# Conn6_5.net
KiCad netlist of a schematic drawn in Altium Designer
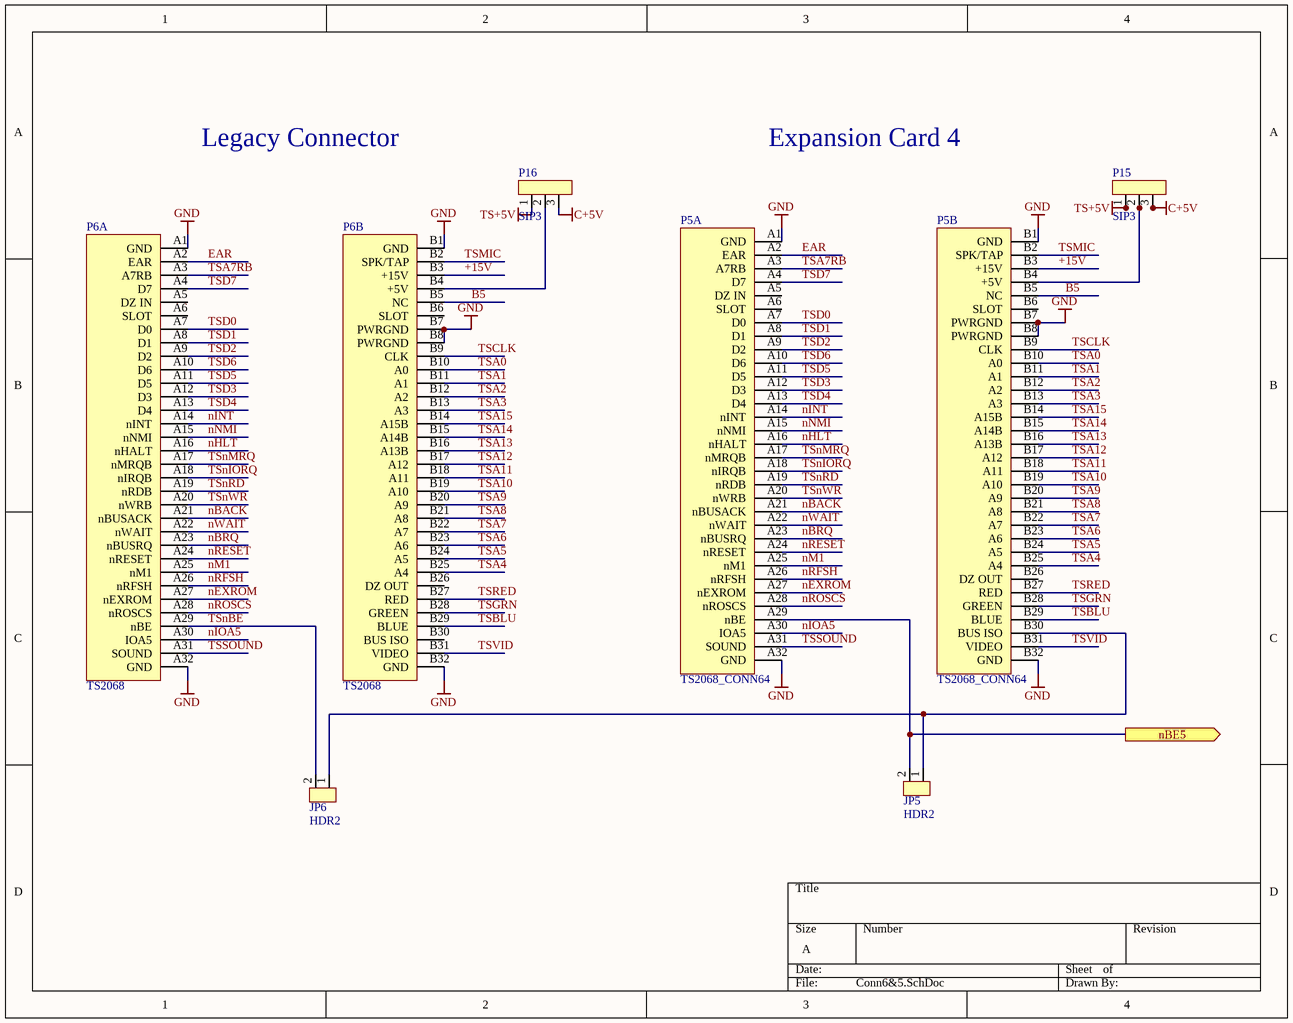
[diagram p0: Conn6&5.SchDoc]

(export (version "E")
  (design (tool "Eeschema 10.0.6"))
  (components
    (comp (ref "JP5") (value "HDR2") (footprint "HDR2") (libsource (lib "Connectors") (part "HDR2")))
    (comp (ref "JP6") (value "HDR2") (footprint "HDR2") (libsource (lib "Connectors") (part "HDR2")))
    (comp (ref "P5")
      (value "TS2068_CONN64")
      (footprint "64CARDEDGE")
      (description "64 Position Female Connector Non Specified - Dual Edge Gold 0.100\" (2.54mm) Black")
      (fields (field (name "MFG") "TD"))
      (libsource (lib "Connectors") (part "TS2068_CONN64"))
    )
    (comp (ref "P6") (value "TS2068") (footprint "TS2068") (libsource (lib "Modules") (part "TS2068")))
    (comp (ref "P15") (value "SIP3") (footprint "SIP3") (libsource (lib "Connectors") (part "SIP3")))
    (comp (ref "P16") (value "SIP3") (footprint "SIP3") (libsource (lib "Connectors") (part "SIP3")))
  )
  (nets
    (net (code "1") (name "/+15V") (class "Default")
      (node (ref "P5") (pin "B3") (pinfunction "+15V_B3") (pintype "passive"))
      (node (ref "P6") (pin "B3") (pinfunction "+15V_B3") (pintype "passive"))
    )
    (net (code "2") (name "/B5") (class "Default")
      (node (ref "P5") (pin "B5") (pinfunction "NC_B5") (pintype "passive"))
      (node (ref "P6") (pin "B5") (pinfunction "NC_B5") (pintype "passive"))
    )
    (net (code "3") (name "/EAR") (class "Default")
      (node (ref "P5") (pin "A2") (pinfunction "EAR_A2") (pintype "passive"))
      (node (ref "P6") (pin "A2") (pinfunction "EAR_A2") (pintype "passive"))
    )
    (net (code "4") (name "/TSA0") (class "Default")
      (node (ref "P5") (pin "B10") (pinfunction "A0_B10") (pintype "passive"))
      (node (ref "P6") (pin "B10") (pinfunction "A0_B10") (pintype "passive"))
    )
    (net (code "5") (name "/TSA1") (class "Default")
      (node (ref "P5") (pin "B11") (pinfunction "A1_B11") (pintype "passive"))
      (node (ref "P6") (pin "B11") (pinfunction "A1_B11") (pintype "passive"))
    )
    (net (code "6") (name "/TSA2") (class "Default")
      (node (ref "P5") (pin "B12") (pinfunction "A2_B12") (pintype "passive"))
      (node (ref "P6") (pin "B12") (pinfunction "A2_B12") (pintype "passive"))
    )
    (net (code "7") (name "/TSA3") (class "Default")
      (node (ref "P5") (pin "B13") (pinfunction "A3_B13") (pintype "passive"))
      (node (ref "P6") (pin "B13") (pinfunction "A3_B13") (pintype "passive"))
    )
    (net (code "8") (name "/TSA4") (class "Default")
      (node (ref "P5") (pin "B25") (pinfunction "A4_B25") (pintype "passive"))
      (node (ref "P6") (pin "B25") (pinfunction "A4_B25") (pintype "passive"))
    )
    (net (code "9") (name "/TSA5") (class "Default")
      (node (ref "P5") (pin "B24") (pinfunction "A5_B24") (pintype "passive"))
      (node (ref "P6") (pin "B24") (pinfunction "A5_B24") (pintype "passive"))
    )
    (net (code "10") (name "/TSA6") (class "Default")
      (node (ref "P5") (pin "B23") (pinfunction "A6_B23") (pintype "passive"))
      (node (ref "P6") (pin "B23") (pinfunction "A6_B23") (pintype "passive"))
    )
    (net (code "11") (name "/TSA7") (class "Default")
      (node (ref "P5") (pin "B22") (pinfunction "A7_B22") (pintype "passive"))
      (node (ref "P6") (pin "B22") (pinfunction "A7_B22") (pintype "passive"))
    )
    (net (code "12") (name "/TSA7RB") (class "Default")
      (node (ref "P5") (pin "A3") (pinfunction "A7RB_A3") (pintype "passive"))
      (node (ref "P6") (pin "A3") (pinfunction "A7RB_A3") (pintype "passive"))
    )
    (net (code "13") (name "/TSA8") (class "Default")
      (node (ref "P5") (pin "B21") (pinfunction "A8_B21") (pintype "passive"))
      (node (ref "P6") (pin "B21") (pinfunction "A8_B21") (pintype "passive"))
    )
    (net (code "14") (name "/TSA9") (class "Default")
      (node (ref "P5") (pin "B20") (pinfunction "A9_B20") (pintype "passive"))
      (node (ref "P6") (pin "B20") (pinfunction "A9_B20") (pintype "passive"))
    )
    (net (code "15") (name "/TSA10") (class "Default")
      (node (ref "P5") (pin "B19") (pinfunction "A10_B19") (pintype "passive"))
      (node (ref "P6") (pin "B19") (pinfunction "A10_B19") (pintype "passive"))
    )
    (net (code "16") (name "/TSA11") (class "Default")
      (node (ref "P5") (pin "B18") (pinfunction "A11_B18") (pintype "passive"))
      (node (ref "P6") (pin "B18") (pinfunction "A11_B18") (pintype "passive"))
    )
    (net (code "17") (name "/TSA12") (class "Default")
      (node (ref "P5") (pin "B17") (pinfunction "A12_B17") (pintype "passive"))
      (node (ref "P6") (pin "B17") (pinfunction "A12_B17") (pintype "passive"))
    )
    (net (code "18") (name "/TSA13") (class "Default")
      (node (ref "P5") (pin "B16") (pinfunction "A13B_B16") (pintype "passive"))
      (node (ref "P6") (pin "B16") (pinfunction "A13B_B16") (pintype "passive"))
    )
    (net (code "19") (name "/TSA14") (class "Default")
      (node (ref "P5") (pin "B15") (pinfunction "A14B_B15") (pintype "passive"))
      (node (ref "P6") (pin "B15") (pinfunction "A14B_B15") (pintype "passive"))
    )
    (net (code "20") (name "/TSA15") (class "Default")
      (node (ref "P5") (pin "B14") (pinfunction "A15B_B14") (pintype "passive"))
      (node (ref "P6") (pin "B14") (pinfunction "A15B_B14") (pintype "passive"))
    )
    (net (code "21") (name "/TSBLU") (class "Default")
      (node (ref "P5") (pin "B29") (pinfunction "BLUE_B29") (pintype "passive"))
      (node (ref "P6") (pin "B29") (pinfunction "BLUE_B29") (pintype "passive"))
    )
    (net (code "22") (name "/TSCLK") (class "Default")
      (node (ref "P5") (pin "B9") (pinfunction "CLK_B9") (pintype "passive"))
      (node (ref "P6") (pin "B9") (pinfunction "CLK_B9") (pintype "passive"))
    )
    (net (code "23") (name "/TSD0") (class "Default")
      (node (ref "P5") (pin "A7") (pinfunction "D0_A7") (pintype "passive"))
      (node (ref "P6") (pin "A7") (pinfunction "D0_A7") (pintype "passive"))
    )
    (net (code "24") (name "/TSD1") (class "Default")
      (node (ref "P5") (pin "A8") (pinfunction "D1_A8") (pintype "passive"))
      (node (ref "P6") (pin "A8") (pinfunction "D1_A8") (pintype "passive"))
    )
    (net (code "25") (name "/TSD2") (class "Default")
      (node (ref "P5") (pin "A9") (pinfunction "D2_A9") (pintype "passive"))
      (node (ref "P6") (pin "A9") (pinfunction "D2_A9") (pintype "passive"))
    )
    (net (code "26") (name "/TSD3") (class "Default")
      (node (ref "P5") (pin "A12") (pinfunction "D3_A12") (pintype "passive"))
      (node (ref "P6") (pin "A12") (pinfunction "D3_A12") (pintype "passive"))
    )
    (net (code "27") (name "/TSD4") (class "Default")
      (node (ref "P5") (pin "A13") (pinfunction "D4_A13") (pintype "passive"))
      (node (ref "P6") (pin "A13") (pinfunction "D4_A13") (pintype "passive"))
    )
    (net (code "28") (name "/TSD5") (class "Default")
      (node (ref "P5") (pin "A11") (pinfunction "D5_A11") (pintype "passive"))
      (node (ref "P6") (pin "A11") (pinfunction "D5_A11") (pintype "passive"))
    )
    (net (code "29") (name "/TSD6") (class "Default")
      (node (ref "P5") (pin "A10") (pinfunction "D6_A10") (pintype "passive"))
      (node (ref "P6") (pin "A10") (pinfunction "D6_A10") (pintype "passive"))
    )
    (net (code "30") (name "/TSD7") (class "Default")
      (node (ref "P5") (pin "A4") (pinfunction "D7_A4") (pintype "passive"))
      (node (ref "P6") (pin "A4") (pinfunction "D7_A4") (pintype "passive"))
    )
    (net (code "31") (name "/TSGRN") (class "Default")
      (node (ref "P5") (pin "B28") (pinfunction "GREEN_B28") (pintype "passive"))
      (node (ref "P6") (pin "B28") (pinfunction "GREEN_B28") (pintype "passive"))
    )
    (net (code "32") (name "/TSMIC") (class "Default")
      (node (ref "P5") (pin "B2") (pinfunction "SPK/TAP_B2") (pintype "passive"))
      (node (ref "P6") (pin "B2") (pinfunction "SPK/TAP_B2") (pintype "passive"))
    )
    (net (code "33") (name "/TSRED") (class "Default")
      (node (ref "P5") (pin "B27") (pinfunction "RED_B27") (pintype "passive"))
      (node (ref "P6") (pin "B27") (pinfunction "RED_B27") (pintype "passive"))
    )
    (net (code "34") (name "/TSSOUND") (class "Default")
      (node (ref "P5") (pin "A31") (pinfunction "SOUND_A31") (pintype "passive"))
      (node (ref "P6") (pin "A31") (pinfunction "SOUND_A31") (pintype "passive"))
    )
    (net (code "35") (name "/TSVID") (class "Default")
      (node (ref "P5") (pin "B31") (pinfunction "VIDEO_B31") (pintype "passive"))
      (node (ref "P6") (pin "B31") (pinfunction "VIDEO_B31") (pintype "passive"))
    )
    (net (code "36") (name "/TSnBE") (class "Default")
      (node (ref "JP6") (pin "2") (pintype "passive"))
      (node (ref "P6") (pin "A29") (pinfunction "nBE_A29") (pintype "passive"))
    )
    (net (code "37") (name "/TSnIORQ") (class "Default")
      (node (ref "P5") (pin "A18") (pinfunction "nIRQB_A18") (pintype "passive"))
      (node (ref "P6") (pin "A18") (pinfunction "nIRQB_A18") (pintype "passive"))
    )
    (net (code "38") (name "/TSnMRQ") (class "Default")
      (node (ref "P5") (pin "A17") (pinfunction "nMRQB_A17") (pintype "passive"))
      (node (ref "P6") (pin "A17") (pinfunction "nMRQB_A17") (pintype "passive"))
    )
    (net (code "39") (name "/TSnRD") (class "Default")
      (node (ref "P5") (pin "A19") (pinfunction "nRDB_A19") (pintype "passive"))
      (node (ref "P6") (pin "A19") (pinfunction "nRDB_A19") (pintype "passive"))
    )
    (net (code "40") (name "/TSnWR") (class "Default")
      (node (ref "P5") (pin "A20") (pinfunction "nWRB_A20") (pintype "passive"))
      (node (ref "P6") (pin "A20") (pinfunction "nWRB_A20") (pintype "passive"))
    )
    (net (code "41") (name "/nBACK") (class "Default")
      (node (ref "P5") (pin "A21") (pinfunction "nBUSACK_A21") (pintype "passive"))
      (node (ref "P6") (pin "A21") (pinfunction "nBUSACK_A21") (pintype "passive"))
    )
    (net (code "42") (name "/nBE5") (class "Default")
      (node (ref "JP5") (pin "2") (pintype "passive"))
      (node (ref "P5") (pin "A29") (pinfunction "nBE_A29") (pintype "passive"))
    )
    (net (code "43") (name "/nBRQ") (class "Default")
      (node (ref "P5") (pin "A23") (pinfunction "nBUSRQ_A23") (pintype "passive"))
      (node (ref "P6") (pin "A23") (pinfunction "nBUSRQ_A23") (pintype "passive"))
    )
    (net (code "44") (name "/nEXROM") (class "Default")
      (node (ref "P5") (pin "A27") (pinfunction "nEXROM_A27") (pintype "passive"))
      (node (ref "P6") (pin "A27") (pinfunction "nEXROM_A27") (pintype "passive"))
    )
    (net (code "45") (name "/nHLT") (class "Default")
      (node (ref "P5") (pin "A16") (pinfunction "nHALT_A16") (pintype "passive"))
      (node (ref "P6") (pin "A16") (pinfunction "nHALT_A16") (pintype "passive"))
    )
    (net (code "46") (name "/nINT") (class "Default")
      (node (ref "P5") (pin "A14") (pinfunction "nINT_A14") (pintype "passive"))
      (node (ref "P6") (pin "A14") (pinfunction "nINT_A14") (pintype "passive"))
    )
    (net (code "47") (name "/nIOA5") (class "Default")
      (node (ref "P5") (pin "A30") (pinfunction "IOA5_A30") (pintype "passive"))
      (node (ref "P6") (pin "A30") (pinfunction "IOA5_A30") (pintype "passive"))
    )
    (net (code "48") (name "/nM1") (class "Default")
      (node (ref "P5") (pin "A25") (pinfunction "nM1_A25") (pintype "passive"))
      (node (ref "P6") (pin "A25") (pinfunction "nM1_A25") (pintype "passive"))
    )
    (net (code "49") (name "/nNMI") (class "Default")
      (node (ref "P5") (pin "A15") (pinfunction "nNMI_A15") (pintype "passive"))
      (node (ref "P6") (pin "A15") (pinfunction "nNMI_A15") (pintype "passive"))
    )
    (net (code "50") (name "/nRESET") (class "Default")
      (node (ref "P5") (pin "A24") (pinfunction "nRESET_A24") (pintype "passive"))
      (node (ref "P6") (pin "A24") (pinfunction "nRESET_A24") (pintype "passive"))
    )
    (net (code "51") (name "/nRFSH") (class "Default")
      (node (ref "P5") (pin "A26") (pinfunction "nRFSH_A26") (pintype "passive"))
      (node (ref "P6") (pin "A26") (pinfunction "nRFSH_A26") (pintype "passive"))
    )
    (net (code "52") (name "/nROSCS") (class "Default")
      (node (ref "P5") (pin "A28") (pinfunction "nROSCS_A28") (pintype "passive"))
      (node (ref "P6") (pin "A28") (pinfunction "nROSCS_A28") (pintype "passive"))
    )
    (net (code "53") (name "/nWAIT") (class "Default")
      (node (ref "P5") (pin "A22") (pinfunction "nWAIT_A22") (pintype "passive"))
      (node (ref "P6") (pin "A22") (pinfunction "nWAIT_A22") (pintype "passive"))
    )
    (net (code "54") (name "C+5V") (class "Default")
      (node (ref "P15") (pin "3") (pintype "passive"))
      (node (ref "P16") (pin "3") (pintype "passive"))
    )
    (net (code "55") (name "GND") (class "Default")
      (node (ref "P5") (pin "A1") (pinfunction "GND_A1") (pintype "passive"))
      (node (ref "P5") (pin "A32") (pinfunction "GND_A32") (pintype "passive"))
      (node (ref "P5") (pin "B1") (pinfunction "GND_B1") (pintype "passive"))
      (node (ref "P5") (pin "B32") (pinfunction "GND_B32") (pintype "passive"))
      (node (ref "P5") (pin "B7") (pinfunction "PWRGND_B7") (pintype "passive"))
      (node (ref "P5") (pin "B8") (pinfunction "PWRGND_B8") (pintype "passive"))
      (node (ref "P6") (pin "A1") (pinfunction "GND_A1") (pintype "passive"))
      (node (ref "P6") (pin "A32") (pinfunction "GND_A32") (pintype "passive"))
      (node (ref "P6") (pin "B1") (pinfunction "GND_B1") (pintype "passive"))
      (node (ref "P6") (pin "B32") (pinfunction "GND_B32") (pintype "passive"))
      (node (ref "P6") (pin "B7") (pinfunction "PWRGND_B7") (pintype "passive"))
      (node (ref "P6") (pin "B8") (pinfunction "PWRGND_B8") (pintype "passive"))
    )
    (net (code "56") (name "Net-(P5B-+5V)") (class "Default")
      (node (ref "P15") (pin "2") (pintype "passive"))
      (node (ref "P5") (pin "B4") (pinfunction "+5V_B4") (pintype "passive"))
    )
    (net (code "57") (name "Net-(P5B-BUS_ISO)") (class "Default")
      (node (ref "JP5") (pin "1") (pintype "passive"))
      (node (ref "JP6") (pin "1") (pintype "passive"))
      (node (ref "P5") (pin "B30") (pinfunction "BUS_ISO_B30") (pintype "passive"))
    )
    (net (code "58") (name "Net-(P6B-+5V)") (class "Default")
      (node (ref "P16") (pin "2") (pintype "passive"))
      (node (ref "P6") (pin "B4") (pinfunction "+5V_B4") (pintype "passive"))
    )
    (net (code "59") (name "TS+5V") (class "Default")
      (node (ref "P15") (pin "1") (pintype "passive"))
      (node (ref "P16") (pin "1") (pintype "passive"))
    )
    (net (code "60") (name "unconnected-(P5A-DZ_IN-PadA5)") (class "Default")
      (node (ref "P5") (pin "A5") (pinfunction "DZ_IN_A5") (pintype "passive"))
    )
    (net (code "61") (name "unconnected-(P5A-SLOT-PadA6)") (class "Default")
      (node (ref "P5") (pin "A6") (pinfunction "SLOT_A6") (pintype "passive"))
    )
    (net (code "62") (name "unconnected-(P5B-DZ_OUT-PadB26)") (class "Default")
      (node (ref "P5") (pin "B26") (pinfunction "DZ_OUT_B26") (pintype "passive"))
    )
    (net (code "63") (name "unconnected-(P5B-SLOT-PadB6)") (class "Default")
      (node (ref "P5") (pin "B6") (pinfunction "SLOT_B6") (pintype "passive"))
    )
    (net (code "64") (name "unconnected-(P6A-DZ_IN-PadA5)") (class "Default")
      (node (ref "P6") (pin "A5") (pinfunction "DZ_IN_A5") (pintype "passive"))
    )
    (net (code "65") (name "unconnected-(P6A-SLOT-PadA6)") (class "Default")
      (node (ref "P6") (pin "A6") (pinfunction "SLOT_A6") (pintype "passive"))
    )
    (net (code "66") (name "unconnected-(P6B-BUS_ISO-PadB30)") (class "Default")
      (node (ref "P6") (pin "B30") (pinfunction "BUS_ISO_B30") (pintype "passive"))
    )
    (net (code "67") (name "unconnected-(P6B-DZ_OUT-PadB26)") (class "Default")
      (node (ref "P6") (pin "B26") (pinfunction "DZ_OUT_B26") (pintype "passive"))
    )
    (net (code "68") (name "unconnected-(P6B-SLOT-PadB6)") (class "Default")
      (node (ref "P6") (pin "B6") (pinfunction "SLOT_B6") (pintype "passive"))
    )
  )
)
